# Boost_Convertor_V2_Schematic.net
KiCad netlist of a schematic drawn in Altium Designer
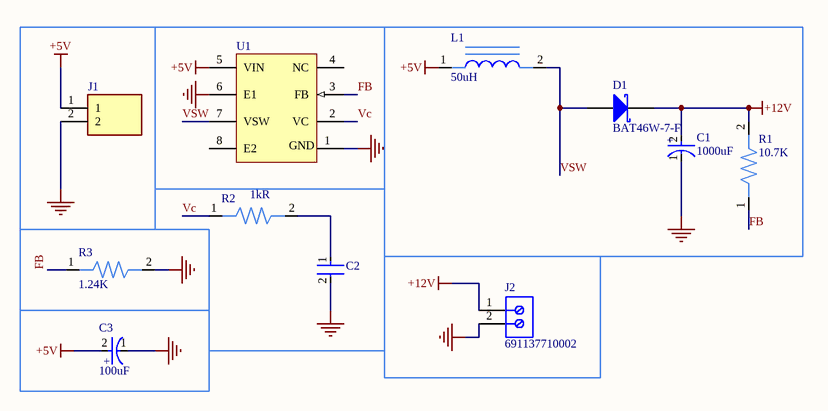
[diagram p0: Boost Convertor V2 Schematic.SchDoc]

(export (version "E")
  (design (tool "Eeschema 10.0.6"))
  (components
    (comp (ref "C1")
      (value "1000uF")
      (footprint "25PX1000MEFCT810X16")
      (fields
        (field (name "MANUFACTURER") "Rubycon")
        (field (name "MANUFACTURER PART NUMBER") "16ZLH1000MEFC10X16")
      )
      (libsource (lib "Boost") (part "16ZLH1000MEFC10X16"))
    )
    (comp (ref "C2")
      (value "CL10B105KA8NNNC")
      (footprint "FP-CL10-IPC_C")
      (description "CAP CER 1UF 25V X7R 0603")
      (fields (field (name "TOLERANCE") "10%") (field (name "VOLTAGE") "25V"))
      (libsource (lib "Altium Content Vault") (part "11868f565c42a9108669ba33697ecf6"))
    )
    (comp (ref "C3")
      (value "100uF")
      (footprint "35ZLH100MEFC6.3X11")
      (description "CAP ALUM 100UF 20% 35V RADIAL")
      (fields (field (name "VOLTAGE") "35V") (field (name "TOLERANCE") "20%"))
      (libsource (lib "Boost") (part "a00bbbee19879c290e62620ae7e47b1"))
    )
    (comp (ref "D1")
      (value "BAT46W-7-F")
      (footprint "DIOD-SOD-123-2_V")
      (description "Surface Mount Schottky Barrier Diode, 100 V, -55 to 125 degC, 2-Pin SOD123, RoHS, Tape and Reel")
      (fields (field (name "MANUFACTURER") "Diodes Inc"))
      (libsource (lib "Altium Content Vault") (part "DIOD-DSKY-A1K2-2"))
    )
    (comp (ref "J1")
      (value "TB005-762-02BE")
      (libsource (lib "Boost Converter Good Copy") (part "TB005-762-02BE"))
    )
    (comp (ref "J2")
      (value "691137710002")
      (footprint "691137710002")
      (libsource (lib "Altium Content Vault") (part "TBL - 1R - 02P - Screw"))
    )
    (comp (ref "L1")
      (value "50uH")
      (footprint "CTX50-1-52-R")
      (description "General Purpose Inductor, 50uH, 1 Element, Iron-Core")
      (fields
        (field (name "MANUFACTURER") "Eaton Cooper")
        (field (name "MANUFACTURER PART NUMBER") "CTX50-1-52-R")
      )
      (libsource (lib "Boost") (part "CTX50-1-52-R"))
    )
    (comp (ref "R1")
      (value "10.7K")
      (footprint "RC0805FR-0710K7L")
      (description "Fixed Resistor, Metal Film, 0.25W, 10700ohm, 250V, 1% +/-Tol, -100,100ppm/Cel")
      (fields
        (field (name "MANUFACTURER") "Yageo")
        (field (name "MANUFACTURER PART NUMBER") "MFR-25FBF52-10K7")
      )
      (libsource (lib "Boost") (part "RC0805FR-0710K7L"))
    )
    (comp (ref "R2")
      (value "1kR")
      (footprint "RC0805FR-071KL")
      (description "Fixed Resistor, Carbon Film, 0.25W, 1000ohm, 350V, 5% +/-Tol, -400,0ppm/Cel, Through Hole Mount")
      (fields
        (field (name "MANUFACTURER") "Stackpole Electronics")
        (field (name "MANUFACTURER PART NUMBER") "CF14JT1K00")
      )
      (libsource (lib "Boost") (part "RC0805FR-071KL"))
    )
    (comp (ref "R3")
      (value "1.24K")
      (footprint "RC0805FR-071K24L")
      (description "Fixed Resistor, Metal Film, 0.25W, 1240ohm, 250V, 1% +/-Tol, -100,100ppm/Cel")
      (fields
        (field (name "MANUFACTURER") "Yageo")
        (field (name "MANUFACTURER PART NUMBER") "MFR-25FBF52-1K24")
      )
      (libsource (lib "Boost") (part "RC0805FR-071K24L"))
    )
    (comp (ref "U1")
      (value "LT1172CN8#PBF")
      (footprint "LT1172CN8#PBF-ND")
      (description "100 kHz, 1.25 A, High Efficiency Switching Regulator, 8-pin DIP (N8-8), 0 to 100 degC, Pb-Free")
      (fields (field (name "MANUFACTURER") "Linear Technology"))
      (libsource (lib "Boost") (part "LT-LT1172-X8-8"))
    )
  )
  (nets
    (net (code "1") (name "+5V") (class "Default")
      (node (ref "C3") (pin "2") (pinfunction "A_2") (pintype "passive"))
      (node (ref "J1") (pin "1") (pinfunction "1_1") (pintype "passive"))
      (node (ref "L1") (pin "1") (pinfunction "1_1") (pintype "passive"))
      (node (ref "U1") (pin "5") (pinfunction "VIN_5") (pintype "power_in"))
    )
    (net (code "2") (name "+12V") (class "Default")
      (node (ref "C1") (pin "2") (pinfunction "A_2") (pintype "passive"))
      (node (ref "D1") (pin "2") (pinfunction "K_2") (pintype "passive"))
      (node (ref "J2") (pin "1") (pinfunction "1_1") (pintype "passive"))
      (node (ref "R1") (pin "2") (pinfunction "2_2") (pintype "passive"))
    )
    (net (code "3") (name "/FB") (class "Default")
      (node (ref "R1") (pin "1") (pinfunction "1_1") (pintype "passive"))
      (node (ref "R3") (pin "1") (pinfunction "1_1") (pintype "passive"))
      (node (ref "U1") (pin "3") (pinfunction "FB_3") (pintype "input"))
    )
    (net (code "4") (name "/VSW") (class "Default")
      (node (ref "D1") (pin "1") (pinfunction "A_1") (pintype "passive"))
      (node (ref "L1") (pin "2") (pinfunction "2_2") (pintype "passive"))
      (node (ref "U1") (pin "7") (pinfunction "VSW_7") (pintype "power_in"))
    )
    (net (code "5") (name "/Vc") (class "Default")
      (node (ref "R2") (pin "1") (pinfunction "1_1") (pintype "passive"))
      (node (ref "U1") (pin "2") (pinfunction "VC_2") (pintype "passive"))
    )
    (net (code "6") (name "GND") (class "Default")
      (node (ref "C1") (pin "1") (pinfunction "C_1") (pintype "passive"))
      (node (ref "C2") (pin "2") (pinfunction "2_2") (pintype "passive"))
      (node (ref "C3") (pin "1") (pinfunction "C_1") (pintype "passive"))
      (node (ref "J1") (pin "2") (pinfunction "2_2") (pintype "passive"))
      (node (ref "J2") (pin "2") (pinfunction "2_2") (pintype "passive"))
      (node (ref "R3") (pin "2") (pinfunction "2_2") (pintype "passive"))
      (node (ref "U1") (pin "6") (pinfunction "E1_6") (pintype "passive"))
    )
    (net (code "7") (name "Net-(C2-Pad1)") (class "Default")
      (node (ref "C2") (pin "1") (pinfunction "1_1") (pintype "passive"))
      (node (ref "R2") (pin "2") (pinfunction "2_2") (pintype "passive"))
    )
    (net (code "8") (name "unconnected-(U1-E2-Pad8)") (class "Default")
      (node (ref "U1") (pin "8") (pinfunction "E2_8") (pintype "passive"))
    )
    (net (code "9") (name "unconnected-(U1-GND-Pad1)") (class "Default")
      (node (ref "U1") (pin "1") (pinfunction "GND_1") (pintype "power_in"))
    )
    (net (code "10") (name "unconnected-(U1-NC-Pad4)") (class "Default")
      (node (ref "U1") (pin "4") (pinfunction "NC_4") (pintype "passive"))
    )
  )
)
